# Micro2440.net
KiCad netlist of a schematic drawn in Altium Designer
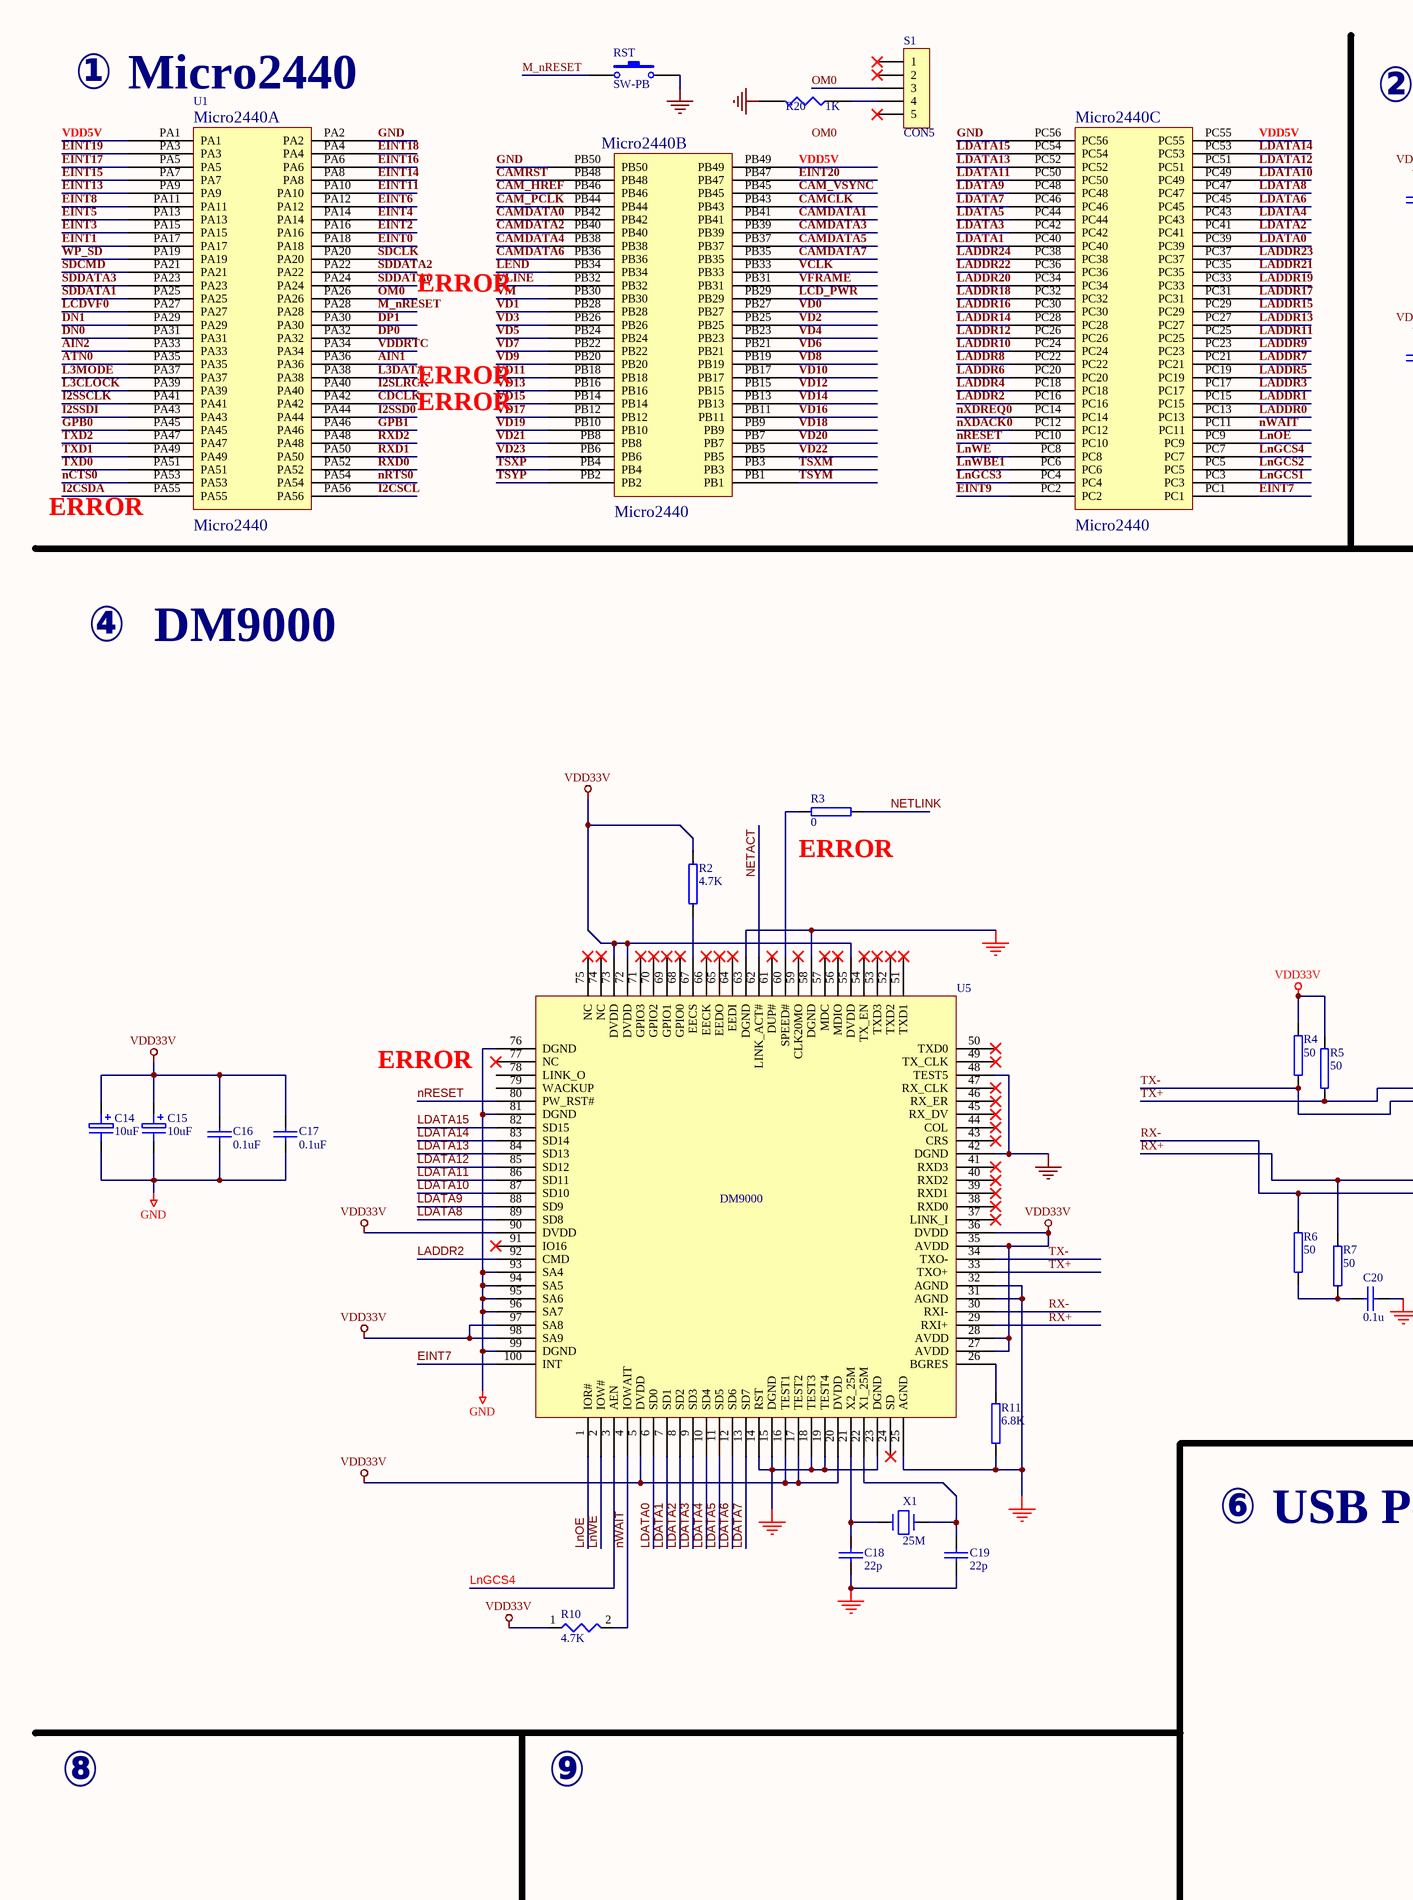
[diagram p0: Micro2440.SchDoc, left]
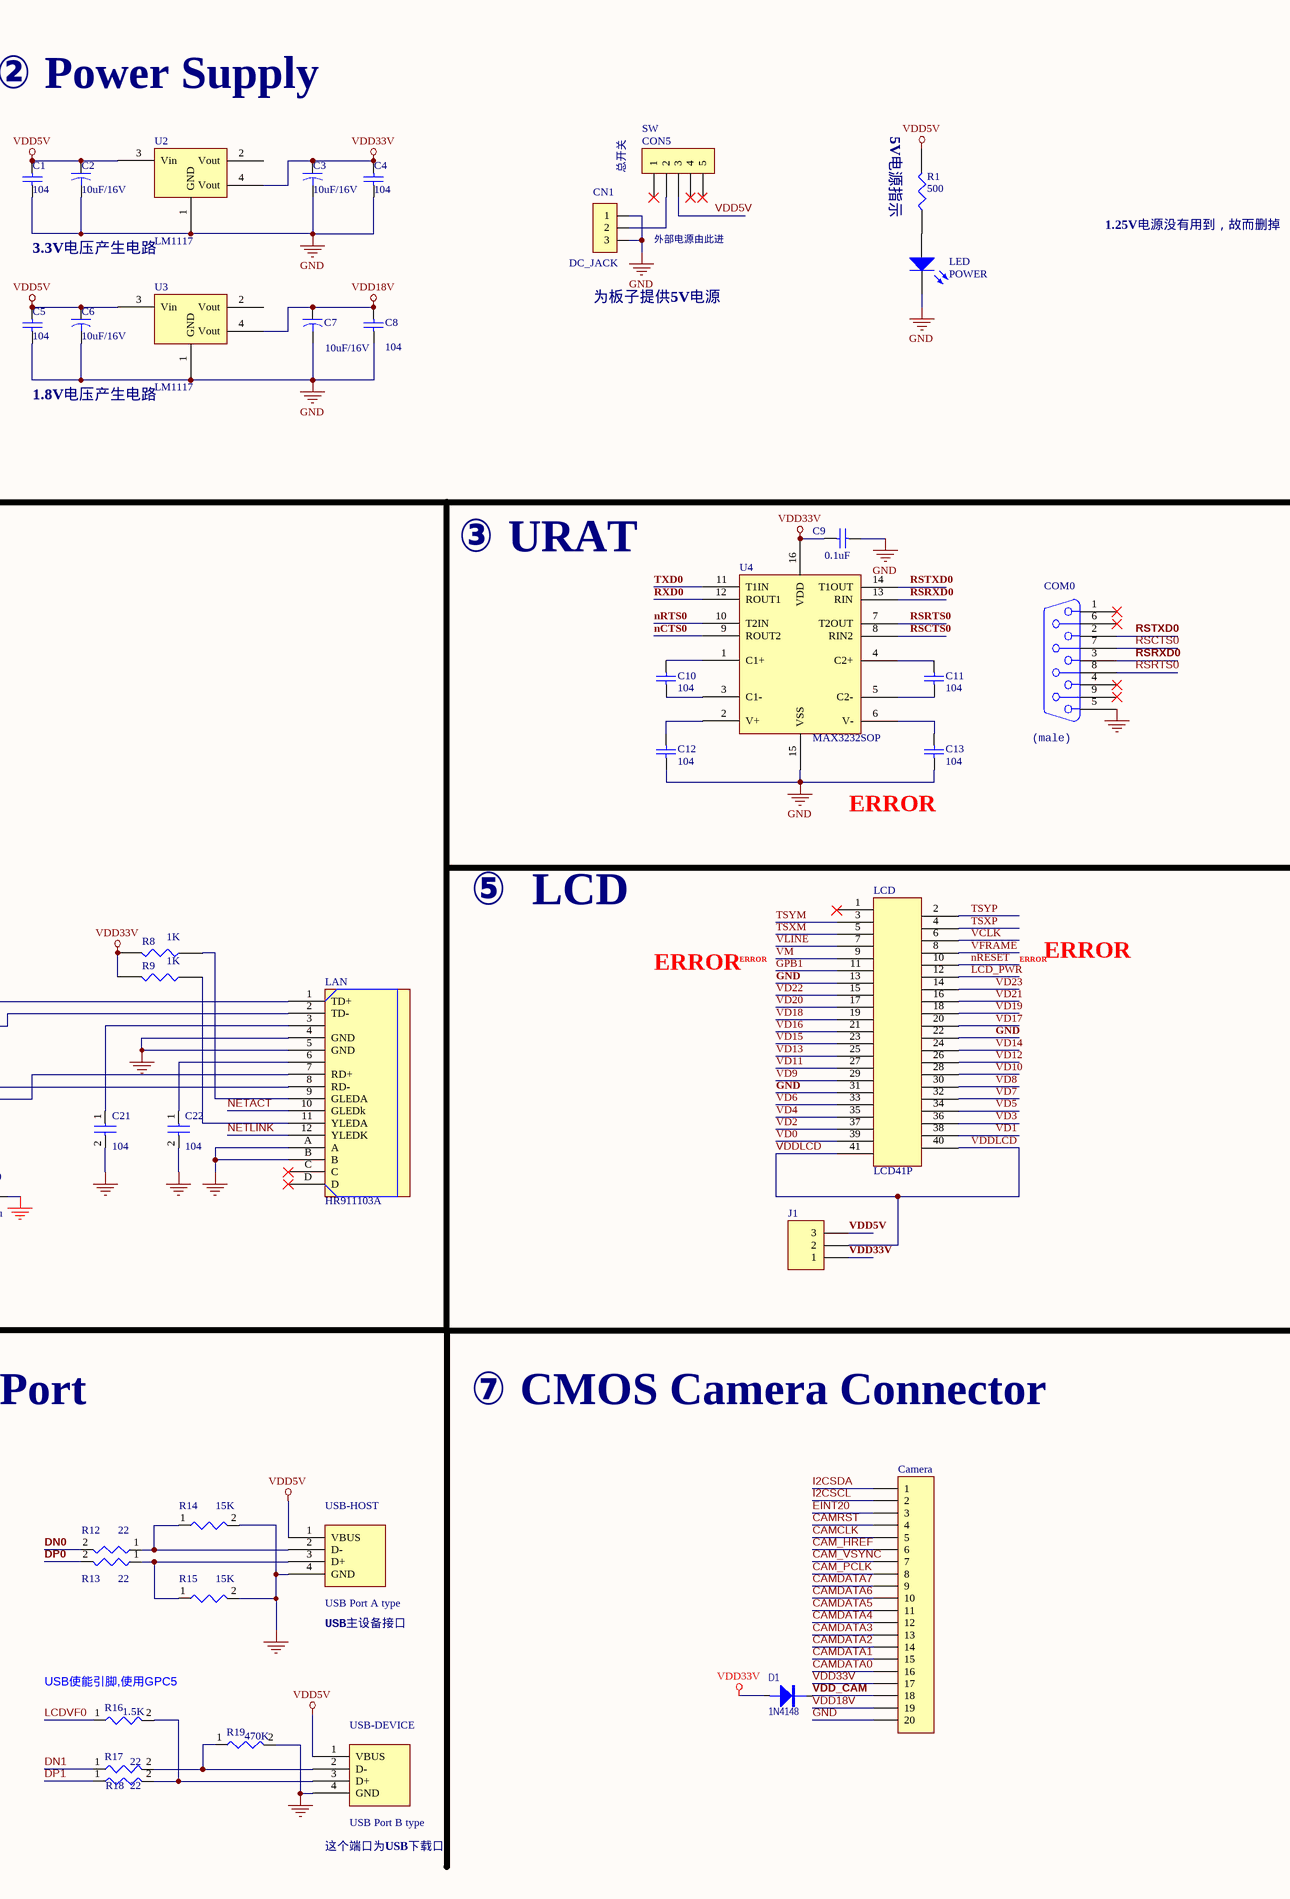
[diagram p1: Micro2440.SchDoc, right]

(export (version "E")
  (design (tool "Eeschema 10.0.6"))
  (components
    (comp (ref "C1")
      (value "104")
      (footprint "0603A")
      (description "Capacitor")
      (fields (field (name "Comment") "Cap") (field (name "PUBLISHER") "Altium Limited"))
      (libsource (lib "Miscellaneous Devices") (part "Cap"))
    )
    (comp (ref "C2")
      (value "10uF/16V")
      (footprint "C3216")
      (description "Capacitor")
      (fields (field (name "Comment") "Cap2") (field (name "PUBLISHER") "Altium Limited"))
      (libsource (lib "Miscellaneous Devices") (part "Cap2"))
    )
    (comp (ref "C3")
      (value "10uF/16V")
      (footprint "C3216")
      (description "Capacitor")
      (fields (field (name "Comment") "Cap2") (field (name "PUBLISHER") "Altium Limited"))
      (libsource (lib "Miscellaneous Devices") (part "Cap2"))
    )
    (comp (ref "C4")
      (value "104")
      (footprint "0603A")
      (description "Capacitor")
      (fields (field (name "Comment") "Cap") (field (name "PUBLISHER") "Altium Limited"))
      (libsource (lib "Miscellaneous Devices") (part "Cap"))
    )
    (comp (ref "C5")
      (value "104")
      (footprint "0603A")
      (description "Capacitor")
      (fields (field (name "Comment") "Cap") (field (name "PUBLISHER") "Altium Limited"))
      (libsource (lib "Miscellaneous Devices") (part "Cap"))
    )
    (comp (ref "C6")
      (value "10uF/16V")
      (footprint "C3216")
      (description "Capacitor")
      (fields (field (name "Comment") "Cap2") (field (name "PUBLISHER") "Altium Limited"))
      (libsource (lib "Miscellaneous Devices") (part "Cap2"))
    )
    (comp (ref "C7")
      (value "10uF/16V")
      (footprint "C3216")
      (description "Capacitor")
      (fields (field (name "Comment") "Cap2") (field (name "PUBLISHER") "Altium Limited"))
      (libsource (lib "Miscellaneous Devices") (part "Cap2"))
    )
    (comp (ref "C8")
      (value "104")
      (footprint "0603A")
      (description "Capacitor")
      (fields (field (name "Comment") "Cap") (field (name "PUBLISHER") "Altium Limited"))
      (libsource (lib "Miscellaneous Devices") (part "Cap"))
    )
    (comp (ref "C9")
      (value "0.1uF")
      (footprint "0603A")
      (description "Capacitor (Semiconductor SIM Model)")
      (fields (field (name "Comment") "Cap Semi") (field (name "PUBLISHER") "Altium Limited"))
      (libsource (lib "Miscellaneous Devices") (part "Cap Semi"))
    )
    (comp (ref "C10")
      (value "104")
      (footprint "0603A")
      (description "Capacitor (Semiconductor SIM Model)")
      (fields (field (name "Comment") "Cap Semi") (field (name "PUBLISHER") "Altium Limited"))
      (libsource (lib "Miscellaneous Devices") (part "Cap Semi"))
    )
    (comp (ref "C11")
      (value "104")
      (footprint "0603A")
      (description "Capacitor (Semiconductor SIM Model)")
      (fields (field (name "Comment") "Cap Semi") (field (name "PUBLISHER") "Altium Limited"))
      (libsource (lib "Miscellaneous Devices") (part "Cap Semi"))
    )
    (comp (ref "C12")
      (value "104")
      (footprint "0603A")
      (description "Capacitor (Semiconductor SIM Model)")
      (fields (field (name "Comment") "Cap Semi") (field (name "PUBLISHER") "Altium Limited"))
      (libsource (lib "Miscellaneous Devices") (part "Cap Semi"))
    )
    (comp (ref "C13")
      (value "104")
      (footprint "0603A")
      (description "Capacitor (Semiconductor SIM Model)")
      (fields (field (name "Comment") "Cap Semi") (field (name "PUBLISHER") "Altium Limited"))
      (libsource (lib "Miscellaneous Devices") (part "Cap Semi"))
    )
    (comp (ref "C14") (value "10uF") (footprint "C3216") (libsource (lib "*") (part "ELECTRO1")))
    (comp (ref "C15") (value "10uF") (footprint "C3216") (libsource (lib "*") (part "ELECTRO1")))
    (comp (ref "C16") (value "0.1uF") (footprint "0603A") (libsource (lib "*") (part "CAP")))
    (comp (ref "C17") (value "0.1uF") (footprint "0603A") (libsource (lib "*") (part "CAP")))
    (comp (ref "C18") (value "22p") (footprint "0603A") (libsource (lib "*") (part "CAP")))
    (comp (ref "C19") (value "22p") (footprint "0603A") (libsource (lib "*") (part "CAP")))
    (comp (ref "C20") (value "0.1u") (footprint "0603A") (libsource (lib "*") (part "CAP")))
    (comp (ref "C21") (value "104") (footprint "0603A") (libsource (lib "*") (part "CAP NP_0")))
    (comp (ref "C22") (value "104") (footprint "0603A") (libsource (lib "*") (part "CAP NP_0")))
    (comp (ref "Camera")
      (value "CON20")
      (footprint "IDC20SS")
      (description "Connector")
      (libsource (lib "*") (part "CON20"))
    )
    (comp (ref "CN1") (value "DC_JACK") (footprint "DC25") (libsource (lib "*") (part "CON3")))
    (comp (ref "COM0") (value "~") (footprint "DB9RA/M") (libsource (lib "*") (part "CONNECTOR DB9")))
    (comp (ref "D1") (value "1N4148") (footprint "D1206") (libsource (lib "*") (part "DIODE")))
    (comp (ref "J1")
      (value "~")
      (footprint "HDR1X3")
      (description "Header, 3-Pin")
      (fields (field (name "PUBLISHER") "Altium Limited"))
      (libsource (lib "Miscellaneous Connectors") (part "Header 3"))
    )
    (comp (ref "LAN") (value "HR911103A") (footprint "HR911103A") (libsource (lib "*") (part "HR911103A")))
    (comp (ref "LCD") (value "LCD41P") (footprint "DF9B-41P-1V2") (libsource (lib "*") (part "LCD41P")))
    (comp (ref "LED")
      (value "POWER")
      (footprint "LED")
      (description "Typical BLUE SiC LED")
      (fields (field (name "PUBLISHER") "Altium Limited"))
      (libsource (lib "Miscellaneous Devices") (part "LED3"))
    )
    (comp (ref "R1") (value "500") (footprint "0603R") (libsource (lib "*") (part "RES1")))
    (comp (ref "R2") (value "4.7K") (footprint "0603R") (libsource (lib "*") (part "RES2")))
    (comp (ref "R3") (value "0") (footprint "0603R") (libsource (lib "*") (part "RES2")))
    (comp (ref "R4") (value "50") (footprint "0603R") (libsource (lib "*") (part "RES2")))
    (comp (ref "R5") (value "50") (footprint "0603R") (libsource (lib "*") (part "RES2")))
    (comp (ref "R6") (value "50") (footprint "0603R") (libsource (lib "*") (part "RES2")))
    (comp (ref "R7") (value "50") (footprint "0603R") (libsource (lib "*") (part "RES2")))
    (comp (ref "R8") (value "1K") (footprint "0603R") (libsource (lib "*") (part "RES1")))
    (comp (ref "R9") (value "1K") (footprint "0603R") (libsource (lib "*") (part "RES1")))
    (comp (ref "R10") (value "4.7K") (footprint "0603R") (libsource (lib "*") (part "R_0")))
    (comp (ref "R11") (value "6.8K") (footprint "0603R") (libsource (lib "*") (part "RES2")))
    (comp (ref "R12") (value "22") (footprint "0603R") (libsource (lib "*") (part "RESISTOR_2")))
    (comp (ref "R13") (value "22") (footprint "0603R") (libsource (lib "*") (part "RESISTOR_2")))
    (comp (ref "R14") (value "15K") (footprint "0603R") (libsource (lib "*") (part "RESISTOR_2")))
    (comp (ref "R15") (value "15K") (footprint "0603R") (libsource (lib "*") (part "RESISTOR_2")))
    (comp (ref "R16") (value "1.5K") (footprint "0603R") (libsource (lib "*") (part "RESISTOR_2")))
    (comp (ref "R17") (value "22") (footprint "0603R") (libsource (lib "*") (part "RESISTOR_2")))
    (comp (ref "R18") (value "22") (footprint "0603R") (libsource (lib "*") (part "RESISTOR_2")))
    (comp (ref "R19") (value "470K") (footprint "0603R") (libsource (lib "*") (part "RESISTOR_2")))
    (comp (ref "R20") (value "1K") (footprint "0603R") (libsource (lib "*") (part "RES1")))
    (comp (ref "RST")
      (value "SW-PB")
      (footprint "RST")
      (description "Switch")
      (fields (field (name "PUBLISHER") "Altium Limited"))
      (libsource (lib "Miscellaneous Devices") (part "SW-PB"))
    )
    (comp (ref "S1")
      (value "CON5")
      (footprint "PCBComponent_1")
      (description "Connector")
      (libsource (lib "") (part "CON5_1"))
    )
    (comp (ref "SW")
      (value "CON5")
      (footprint "Micro2440_LIB:PCBComponent_1")
      (description "Connector")
      (libsource (lib "*") (part "CON5"))
    )
    (comp (ref "U1")
      (value "Micro2440")
      (footprint "Micro2440SDK:MICRO2440")
      (libsource (lib "MICRO2440_01") (part "Component_1"))
    )
    (comp (ref "U2") (value "LM1117") (footprint "SOT223S") (libsource (lib "MICRO2440_LIB") (part "LM1117")))
    (comp (ref "U3") (value "LM1117") (footprint "SOT223S") (libsource (lib "MICRO2440_LIB") (part "LM1117")))
    (comp (ref "U4")
      (value "MAX3232SOP")
      (footprint "SSOP16")
      (libsource (lib "MAX3232SOP") (part "Component_1"))
    )
    (comp (ref "U5") (value "DM9000") (footprint "QFP100") (libsource (lib "*") (part "DM9000")))
    (comp (ref "USB-DEVICE")
      (value "USB Port B type")
      (footprint "USB-B")
      (libsource (lib "*") (part "USBPORT"))
    )
    (comp (ref "USB-HOST")
      (value "USB Port A type")
      (footprint "USB-A")
      (libsource (lib "*") (part "USBPORT"))
    )
    (comp (ref "X1") (value "25M") (footprint "OSC2PR-1") (libsource (lib "*") (part "CRYSTAL")))
  )
  (nets
    (net (code "1") (name "/AIN1") (class "Default")
      (node (ref "U1") (pin "PA36") (pinfunction "PA36_PA36") (pintype "passive"))
    )
    (net (code "2") (name "/AIN2") (class "Default")
      (node (ref "U1") (pin "PA33") (pinfunction "PA33_PA33") (pintype "passive"))
    )
    (net (code "3") (name "/ATN0") (class "Default")
      (node (ref "U1") (pin "PA35") (pinfunction "PA35_PA35") (pintype "passive"))
    )
    (net (code "4") (name "/CAMCLK") (class "Default")
      (node (ref "Camera") (pin "5") (pinfunction "5_5") (pintype "passive"))
      (node (ref "U1") (pin "PB43") (pinfunction "PB43_PB43") (pintype "passive"))
    )
    (net (code "5") (name "/CAMDATA0") (class "Default")
      (node (ref "Camera") (pin "16") (pinfunction "16_16") (pintype "passive"))
      (node (ref "U1") (pin "PB42") (pinfunction "PB42_PB42") (pintype "passive"))
    )
    (net (code "6") (name "/CAMDATA1") (class "Default")
      (node (ref "Camera") (pin "15") (pinfunction "15_15") (pintype "passive"))
      (node (ref "U1") (pin "PB41") (pinfunction "PB41_PB41") (pintype "passive"))
    )
    (net (code "7") (name "/CAMDATA2") (class "Default")
      (node (ref "Camera") (pin "14") (pinfunction "14_14") (pintype "passive"))
      (node (ref "U1") (pin "PB40") (pinfunction "PB40_PB40") (pintype "passive"))
    )
    (net (code "8") (name "/CAMDATA3") (class "Default")
      (node (ref "Camera") (pin "13") (pinfunction "13_13") (pintype "passive"))
      (node (ref "U1") (pin "PB39") (pinfunction "PB39_PB39") (pintype "passive"))
    )
    (net (code "9") (name "/CAMDATA4") (class "Default")
      (node (ref "Camera") (pin "12") (pinfunction "12_12") (pintype "passive"))
      (node (ref "U1") (pin "PB38") (pinfunction "PB38_PB38") (pintype "passive"))
    )
    (net (code "10") (name "/CAMDATA5") (class "Default")
      (node (ref "Camera") (pin "11") (pinfunction "11_11") (pintype "passive"))
      (node (ref "U1") (pin "PB37") (pinfunction "PB37_PB37") (pintype "passive"))
    )
    (net (code "11") (name "/CAMDATA6") (class "Default")
      (node (ref "Camera") (pin "10") (pinfunction "10_10") (pintype "passive"))
      (node (ref "U1") (pin "PB36") (pinfunction "PB36_PB36") (pintype "passive"))
    )
    (net (code "12") (name "/CAMDATA7") (class "Default")
      (node (ref "Camera") (pin "9") (pinfunction "9_9") (pintype "passive"))
      (node (ref "U1") (pin "PB35") (pinfunction "PB35_PB35") (pintype "passive"))
    )
    (net (code "13") (name "/CAMRST") (class "Default")
      (node (ref "Camera") (pin "4") (pinfunction "4_4") (pintype "passive"))
      (node (ref "U1") (pin "PB48") (pinfunction "PB48_PB48") (pintype "passive"))
    )
    (net (code "14") (name "/CAM_HREF") (class "Default")
      (node (ref "Camera") (pin "6") (pinfunction "6_6") (pintype "passive"))
      (node (ref "U1") (pin "PB46") (pinfunction "PB46_PB46") (pintype "passive"))
    )
    (net (code "15") (name "/CAM_PCLK") (class "Default")
      (node (ref "Camera") (pin "8") (pinfunction "8_8") (pintype "passive"))
      (node (ref "U1") (pin "PB44") (pinfunction "PB44_PB44") (pintype "passive"))
    )
    (net (code "16") (name "/CAM_VSYNC") (class "Default")
      (node (ref "Camera") (pin "7") (pinfunction "7_7") (pintype "passive"))
      (node (ref "U1") (pin "PB45") (pinfunction "PB45_PB45") (pintype "passive"))
    )
    (net (code "17") (name "/CDCLK") (class "Default")
      (node (ref "U1") (pin "PA42") (pinfunction "PA42_PA42") (pintype "passive"))
    )
    (net (code "18") (name "/DN0") (class "Default")
      (node (ref "R12") (pin "2") (pinfunction "2_2") (pintype "passive"))
      (node (ref "U1") (pin "PA31") (pinfunction "PA31_PA31") (pintype "passive"))
    )
    (net (code "19") (name "/DN1") (class "Default")
      (node (ref "R17") (pin "1") (pinfunction "1_1") (pintype "passive"))
      (node (ref "U1") (pin "PA29") (pinfunction "PA29_PA29") (pintype "passive"))
    )
    (net (code "20") (name "/DP0") (class "Default")
      (node (ref "R13") (pin "2") (pinfunction "2_2") (pintype "passive"))
      (node (ref "U1") (pin "PA32") (pinfunction "PA32_PA32") (pintype "passive"))
    )
    (net (code "21") (name "/DP1") (class "Default")
      (node (ref "R18") (pin "1") (pinfunction "1_1") (pintype "passive"))
      (node (ref "U1") (pin "PA30") (pinfunction "PA30_PA30") (pintype "passive"))
    )
    (net (code "22") (name "/EINT0") (class "Default")
      (node (ref "U1") (pin "PA18") (pinfunction "PA18_PA18") (pintype "passive"))
    )
    (net (code "23") (name "/EINT1") (class "Default")
      (node (ref "U1") (pin "PA17") (pinfunction "PA17_PA17") (pintype "passive"))
    )
    (net (code "24") (name "/EINT2") (class "Default")
      (node (ref "U1") (pin "PA16") (pinfunction "PA16_PA16") (pintype "passive"))
    )
    (net (code "25") (name "/EINT3") (class "Default")
      (node (ref "U1") (pin "PA15") (pinfunction "PA15_PA15") (pintype "passive"))
    )
    (net (code "26") (name "/EINT4") (class "Default")
      (node (ref "U1") (pin "PA14") (pinfunction "PA14_PA14") (pintype "passive"))
    )
    (net (code "27") (name "/EINT5") (class "Default")
      (node (ref "U1") (pin "PA13") (pinfunction "PA13_PA13") (pintype "passive"))
    )
    (net (code "28") (name "/EINT6") (class "Default")
      (node (ref "U1") (pin "PA12") (pinfunction "PA12_PA12") (pintype "passive"))
    )
    (net (code "29") (name "/EINT7") (class "Default")
      (node (ref "U1") (pin "PC1") (pinfunction "PC1_PC1") (pintype "passive"))
      (node (ref "U5") (pin "100") (pinfunction "INT_100") (pintype "passive"))
    )
    (net (code "30") (name "/EINT8") (class "Default")
      (node (ref "U1") (pin "PA11") (pinfunction "PA11_PA11") (pintype "passive"))
    )
    (net (code "31") (name "/EINT9") (class "Default")
      (node (ref "U1") (pin "PC2") (pinfunction "PC2_PC2") (pintype "passive"))
    )
    (net (code "32") (name "/EINT11") (class "Default")
      (node (ref "U1") (pin "PA10") (pinfunction "PA10_PA10") (pintype "passive"))
    )
    (net (code "33") (name "/EINT13") (class "Default")
      (node (ref "U1") (pin "PA9") (pinfunction "PA9_PA9") (pintype "passive"))
    )
    (net (code "34") (name "/EINT14") (class "Default")
      (node (ref "U1") (pin "PA8") (pinfunction "PA8_PA8") (pintype "passive"))
    )
    (net (code "35") (name "/EINT15") (class "Default")
      (node (ref "U1") (pin "PA7") (pinfunction "PA7_PA7") (pintype "passive"))
    )
    (net (code "36") (name "/EINT16") (class "Default")
      (node (ref "U1") (pin "PA6") (pinfunction "PA6_PA6") (pintype "passive"))
    )
    (net (code "37") (name "/EINT17") (class "Default")
      (node (ref "U1") (pin "PA5") (pinfunction "PA5_PA5") (pintype "passive"))
    )
    (net (code "38") (name "/EINT18") (class "Default")
      (node (ref "U1") (pin "PA4") (pinfunction "PA4_PA4") (pintype "passive"))
    )
    (net (code "39") (name "/EINT19") (class "Default")
      (node (ref "U1") (pin "PA3") (pinfunction "PA3_PA3") (pintype "passive"))
    )
    (net (code "40") (name "/EINT20") (class "Default")
      (node (ref "Camera") (pin "3") (pinfunction "3_3") (pintype "passive"))
      (node (ref "U1") (pin "PB47") (pinfunction "PB47_PB47") (pintype "passive"))
    )
    (net (code "41") (name "/GPB0") (class "Default")
      (node (ref "U1") (pin "PA45") (pinfunction "PA45_PA45") (pintype "passive"))
    )
    (net (code "42") (name "/GPB1") (class "Default")
      (node (ref "LCD") (pin "11") (pintype "passive"))
      (node (ref "U1") (pin "PA46") (pinfunction "PA46_PA46") (pintype "passive"))
    )
    (net (code "43") (name "/I2CSCL") (class "Default")
      (node (ref "Camera") (pin "2") (pinfunction "2_2") (pintype "passive"))
      (node (ref "U1") (pin "PA56") (pinfunction "PA56_PA56") (pintype "passive"))
    )
    (net (code "44") (name "/I2CSDA") (class "Default")
      (node (ref "Camera") (pin "1") (pinfunction "1_1") (pintype "passive"))
      (node (ref "U1") (pin "PA55") (pinfunction "PA55_PA55") (pintype "passive"))
    )
    (net (code "45") (name "/I2SLRCK") (class "Default")
      (node (ref "U1") (pin "PA40") (pinfunction "PA40_PA40") (pintype "passive"))
    )
    (net (code "46") (name "/I2SSCLK") (class "Default")
      (node (ref "U1") (pin "PA41") (pinfunction "PA41_PA41") (pintype "passive"))
    )
    (net (code "47") (name "/I2SSD0") (class "Default")
      (node (ref "U1") (pin "PA44") (pinfunction "PA44_PA44") (pintype "passive"))
    )
    (net (code "48") (name "/I2SSDI") (class "Default")
      (node (ref "U1") (pin "PA43") (pinfunction "PA43_PA43") (pintype "passive"))
    )
    (net (code "49") (name "/L3CLOCK") (class "Default")
      (node (ref "U1") (pin "PA39") (pinfunction "PA39_PA39") (pintype "passive"))
    )
    (net (code "50") (name "/L3DATA") (class "Default")
      (node (ref "U1") (pin "PA38") (pinfunction "PA38_PA38") (pintype "passive"))
    )
    (net (code "51") (name "/L3MODE") (class "Default")
      (node (ref "U1") (pin "PA37") (pinfunction "PA37_PA37") (pintype "passive"))
    )
    (net (code "52") (name "/LADDR0") (class "Default")
      (node (ref "U1") (pin "PC13") (pinfunction "PC13_PC13") (pintype "passive"))
    )
    (net (code "53") (name "/LADDR1") (class "Default")
      (node (ref "U1") (pin "PC15") (pinfunction "PC15_PC15") (pintype "passive"))
    )
    (net (code "54") (name "/LADDR2") (class "Default")
      (node (ref "U1") (pin "PC16") (pinfunction "PC16_PC16") (pintype "passive"))
      (node (ref "U5") (pin "92") (pinfunction "CMD_92") (pintype "passive"))
    )
    (net (code "55") (name "/LADDR3") (class "Default")
      (node (ref "U1") (pin "PC17") (pinfunction "PC17_PC17") (pintype "passive"))
    )
    (net (code "56") (name "/LADDR4") (class "Default")
      (node (ref "U1") (pin "PC18") (pinfunction "PC18_PC18") (pintype "passive"))
    )
    (net (code "57") (name "/LADDR5") (class "Default")
      (node (ref "U1") (pin "PC19") (pinfunction "PC19_PC19") (pintype "passive"))
    )
    (net (code "58") (name "/LADDR6") (class "Default")
      (node (ref "U1") (pin "PC20") (pinfunction "PC20_PC20") (pintype "passive"))
    )
    (net (code "59") (name "/LADDR7") (class "Default")
      (node (ref "U1") (pin "PC21") (pinfunction "PC21_PC21") (pintype "passive"))
    )
    (net (code "60") (name "/LADDR8") (class "Default")
      (node (ref "U1") (pin "PC22") (pinfunction "PC22_PC22") (pintype "passive"))
    )
    (net (code "61") (name "/LADDR9") (class "Default")
      (node (ref "U1") (pin "PC23") (pinfunction "PC23_PC23") (pintype "passive"))
    )
    (net (code "62") (name "/LADDR10") (class "Default")
      (node (ref "U1") (pin "PC24") (pinfunction "PC24_PC24") (pintype "passive"))
    )
    (net (code "63") (name "/LADDR11") (class "Default")
      (node (ref "U1") (pin "PC25") (pinfunction "PC25_PC25") (pintype "passive"))
    )
    (net (code "64") (name "/LADDR12") (class "Default")
      (node (ref "U1") (pin "PC26") (pinfunction "PC26_PC26") (pintype "passive"))
    )
    (net (code "65") (name "/LADDR13") (class "Default")
      (node (ref "U1") (pin "PC27") (pinfunction "PC27_PC27") (pintype "passive"))
    )
    (net (code "66") (name "/LADDR14") (class "Default")
      (node (ref "U1") (pin "PC28") (pinfunction "PC28_PC28") (pintype "passive"))
    )
    (net (code "67") (name "/LADDR15") (class "Default")
      (node (ref "U1") (pin "PC29") (pinfunction "PC29_PC29") (pintype "passive"))
    )
    (net (code "68") (name "/LADDR16") (class "Default")
      (node (ref "U1") (pin "PC30") (pinfunction "PC30_PC30") (pintype "passive"))
    )
    (net (code "69") (name "/LADDR17") (class "Default")
      (node (ref "U1") (pin "PC31") (pinfunction "PC31_PC31") (pintype "passive"))
    )
    (net (code "70") (name "/LADDR18") (class "Default")
      (node (ref "U1") (pin "PC32") (pinfunction "PC32_PC32") (pintype "passive"))
    )
    (net (code "71") (name "/LADDR19") (class "Default")
      (node (ref "U1") (pin "PC33") (pinfunction "PC33_PC33") (pintype "passive"))
    )
    (net (code "72") (name "/LADDR20") (class "Default")
      (node (ref "U1") (pin "PC34") (pinfunction "PC34_PC34") (pintype "passive"))
    )
    (net (code "73") (name "/LADDR21") (class "Default")
      (node (ref "U1") (pin "PC35") (pinfunction "PC35_PC35") (pintype "passive"))
    )
    (net (code "74") (name "/LADDR22") (class "Default")
      (node (ref "U1") (pin "PC36") (pinfunction "PC36_PC36") (pintype "passive"))
    )
    (net (code "75") (name "/LADDR23") (class "Default")
      (node (ref "U1") (pin "PC37") (pinfunction "PC37_PC37") (pintype "passive"))
    )
    (net (code "76") (name "/LADDR24") (class "Default")
      (node (ref "U1") (pin "PC38") (pinfunction "PC38_PC38") (pintype "passive"))
    )
    (net (code "77") (name "/LCDVF0") (class "Default")
      (node (ref "R16") (pin "1") (pinfunction "1_1") (pintype "passive"))
      (node (ref "U1") (pin "PA27") (pinfunction "PA27_PA27") (pintype "passive"))
    )
    (net (code "78") (name "/LCD_PWR") (class "Default")
      (node (ref "LCD") (pin "12") (pintype "passive"))
      (node (ref "U1") (pin "PB29") (pinfunction "PB29_PB29") (pintype "passive"))
    )
    (net (code "79") (name "/LDATA0") (class "Default")
      (node (ref "U1") (pin "PC39") (pinfunction "PC39_PC39") (pintype "passive"))
      (node (ref "U5") (pin "6") (pinfunction "SD0_6") (pintype "passive"))
    )
    (net (code "80") (name "/LDATA1") (class "Default")
      (node (ref "U1") (pin "PC40") (pinfunction "PC40_PC40") (pintype "passive"))
      (node (ref "U5") (pin "7") (pinfunction "SD1_7") (pintype "passive"))
    )
    (net (code "81") (name "/LDATA2") (class "Default")
      (node (ref "U1") (pin "PC41") (pinfunction "PC41_PC41") (pintype "passive"))
      (node (ref "U5") (pin "8") (pinfunction "SD2_8") (pintype "passive"))
    )
    (net (code "82") (name "/LDATA3") (class "Default")
      (node (ref "U1") (pin "PC42") (pinfunction "PC42_PC42") (pintype "passive"))
      (node (ref "U5") (pin "9") (pinfunction "SD3_9") (pintype "passive"))
    )
    (net (code "83") (name "/LDATA4") (class "Default")
      (node (ref "U1") (pin "PC43") (pinfunction "PC43_PC43") (pintype "passive"))
      (node (ref "U5") (pin "10") (pinfunction "SD4_10") (pintype "passive"))
    )
    (net (code "84") (name "/LDATA5") (class "Default")
      (node (ref "U1") (pin "PC44") (pinfunction "PC44_PC44") (pintype "passive"))
      (node (ref "U5") (pin "11") (pinfunction "SD5_11") (pintype "passive"))
    )
    (net (code "85") (name "/LDATA6") (class "Default")
      (node (ref "U1") (pin "PC45") (pinfunction "PC45_PC45") (pintype "passive"))
      (node (ref "U5") (pin "12") (pinfunction "SD6_12") (pintype "passive"))
    )
    (net (code "86") (name "/LDATA7") (class "Default")
      (node (ref "U1") (pin "PC46") (pinfunction "PC46_PC46") (pintype "passive"))
      (node (ref "U5") (pin "13") (pinfunction "SD7_13") (pintype "passive"))
    )
    (net (code "87") (name "/LDATA8") (class "Default")
      (node (ref "U1") (pin "PC47") (pinfunction "PC47_PC47") (pintype "passive"))
      (node (ref "U5") (pin "89") (pinfunction "SD8_89") (pintype "passive"))
    )
    (net (code "88") (name "/LDATA9") (class "Default")
      (node (ref "U1") (pin "PC48") (pinfunction "PC48_PC48") (pintype "passive"))
      (node (ref "U5") (pin "88") (pinfunction "SD9_88") (pintype "passive"))
    )
    (net (code "89") (name "/LDATA10") (class "Default")
      (node (ref "U1") (pin "PC49") (pinfunction "PC49_PC49") (pintype "passive"))
      (node (ref "U5") (pin "87") (pinfunction "SD10_87") (pintype "passive"))
    )
    (net (code "90") (name "/LDATA11") (class "Default")
      (node (ref "U1") (pin "PC50") (pinfunction "PC50_PC50") (pintype "passive"))
      (node (ref "U5") (pin "86") (pinfunction "SD11_86") (pintype "passive"))
    )
    (net (code "91") (name "/LDATA12") (class "Default")
      (node (ref "U1") (pin "PC51") (pinfunction "PC51_PC51") (pintype "passive"))
      (node (ref "U5") (pin "85") (pinfunction "SD12_85") (pintype "passive"))
    )
    (net (code "92") (name "/LDATA13") (class "Default")
      (node (ref "U1") (pin "PC52") (pinfunction "PC52_PC52") (pintype "passive"))
      (node (ref "U5") (pin "84") (pinfunction "SD13_84") (pintype "passive"))
    )
    (net (code "93") (name "/LDATA14") (class "Default")
      (node (ref "U1") (pin "PC53") (pinfunction "PC53_PC53") (pintype "passive"))
      (node (ref "U5") (pin "83") (pinfunction "SD14_83") (pintype "passive"))
    )
    (net (code "94") (name "/LDATA15") (class "Default")
      (node (ref "U1") (pin "PC54") (pinfunction "PC54_PC54") (pintype "passive"))
      (node (ref "U5") (pin "82") (pinfunction "SD15_82") (pintype "passive"))
    )
    (net (code "95") (name "/LEND") (class "Default")
      (node (ref "U1") (pin "PB34") (pinfunction "PB34_PB34") (pintype "passive"))
    )
    (net (code "96") (name "/LnGCS1") (class "Default")
      (node (ref "U1") (pin "PC3") (pinfunction "PC3_PC3") (pintype "passive"))
    )
    (net (code "97") (name "/LnGCS2") (class "Default")
      (node (ref "U1") (pin "PC5") (pinfunction "PC5_PC5") (pintype "passive"))
    )
    (net (code "98") (name "/LnGCS3") (class "Default")
      (node (ref "U1") (pin "PC4") (pinfunction "PC4_PC4") (pintype "passive"))
    )
    (net (code "99") (name "/LnGCS4") (class "Default")
      (node (ref "U1") (pin "PC7") (pinfunction "PC7_PC7") (pintype "passive"))
      (node (ref "U5") (pin "3") (pinfunction "AEN_3") (pintype "passive"))
    )
    (net (code "100") (name "/LnOE") (class "Default")
      (node (ref "U1") (pin "PC9") (pinfunction "PC9_PC9") (pintype "passive"))
      (node (ref "U5") (pin "1") (pinfunction "IOR#_1") (pintype "passive"))
    )
    (net (code "101") (name "/LnWBE1") (class "Default")
      (node (ref "U1") (pin "PC6") (pinfunction "PC6_PC6") (pintype "passive"))
    )
    (net (code "102") (name "/LnWE") (class "Default")
      (node (ref "U1") (pin "PC8") (pinfunction "PC8_PC8") (pintype "passive"))
      (node (ref "U5") (pin "2") (pinfunction "IOW#_2") (pintype "passive"))
    )
    (net (code "103") (name "/M_nRESET") (class "Default")
      (node (ref "RST") (pin "1") (pinfunction "1_1") (pintype "passive"))
      (node (ref "U1") (pin "PA28") (pinfunction "PA28_PA28") (pintype "passive"))
    )
    (net (code "104") (name "/NETACT") (class "Default")
      (node (ref "LAN") (pin "10") (pinfunction "GLEDk_10") (pintype "passive"))
      (node (ref "U5") (pin "62") (pinfunction "LINK_ACT#_62") (pintype "passive"))
    )
    (net (code "105") (name "/NETLINK") (class "Default")
      (node (ref "LAN") (pin "12") (pinfunction "YLEDK_12") (pintype "passive"))
      (node (ref "R3") (pin "1") (pintype "passive"))
    )
    (net (code "106") (name "/OM0") (class "Default")
      (node (ref "S1") (pin "3") (pinfunction "3_3") (pintype "passive"))
      (node (ref "U1") (pin "PA26") (pinfunction "PA26_PA26") (pintype "passive"))
    )
    (net (code "107") (name "/RSCTS0") (class "Default")
      (node (ref "COM0") (pin "7") (pinfunction "7_7") (pintype "passive"))
      (node (ref "U4") (pin "8") (pinfunction "RIN2_8") (pintype "passive"))
    )
    (net (code "108") (name "/RSRTS0") (class "Default")
      (node (ref "COM0") (pin "8") (pinfunction "8_8") (pintype "passive"))
      (node (ref "U4") (pin "7") (pinfunction "T2OUT_7") (pintype "passive"))
    )
    (net (code "109") (name "/RSRXD0") (class "Default")
      (node (ref "COM0") (pin "3") (pinfunction "3_3") (pintype "passive"))
      (node (ref "U4") (pin "13") (pinfunction "RIN_13") (pintype "passive"))
    )
    (net (code "110") (name "/RSTXD0") (class "Default")
      (node (ref "COM0") (pin "2") (pinfunction "2_2") (pintype "passive"))
      (node (ref "U4") (pin "14") (pinfunction "T1OUT_14") (pintype "passive"))
    )
    (net (code "111") (name "/RX+") (class "Default")
      (node (ref "LAN") (pin "8") (pinfunction "RD-_8") (pintype "passive"))
      (node (ref "R7") (pin "2") (pintype "passive"))
      (node (ref "U5") (pin "29") (pinfunction "RXI+_29") (pintype "passive"))
    )
    (net (code "112") (name "/RX-") (class "Default")
      (node (ref "LAN") (pin "7") (pinfunction "RD+_7") (pintype "passive"))
      (node (ref "R6") (pin "2") (pintype "passive"))
      (node (ref "U5") (pin "30") (pinfunction "RXI-_30") (pintype "passive"))
    )
    (net (code "113") (name "/RXD0") (class "Default")
      (node (ref "U1") (pin "PA52") (pinfunction "PA52_PA52") (pintype "passive"))
      (node (ref "U4") (pin "12") (pinfunction "ROUT1_12") (pintype "passive"))
    )
    (net (code "114") (name "/RXD1") (class "Default")
      (node (ref "U1") (pin "PA50") (pinfunction "PA50_PA50") (pintype "passive"))
    )
    (net (code "115") (name "/RXD2") (class "Default")
      (node (ref "U1") (pin "PA48") (pinfunction "PA48_PA48") (pintype "passive"))
    )
    (net (code "116") (name "/SDCLK") (class "Default")
      (node (ref "U1") (pin "PA20") (pinfunction "PA20_PA20") (pintype "passive"))
    )
    (net (code "117") (name "/SDCMD") (class "Default")
      (node (ref "U1") (pin "PA21") (pinfunction "PA21_PA21") (pintype "passive"))
    )
    (net (code "118") (name "/SDDATA0") (class "Default")
      (node (ref "U1") (pin "PA24") (pinfunction "PA24_PA24") (pintype "passive"))
    )
    (net (code "119") (name "/SDDATA1") (class "Default")
      (node (ref "U1") (pin "PA25") (pinfunction "PA25_PA25") (pintype "passive"))
    )
    (net (code "120") (name "/SDDATA2") (class "Default")
      (node (ref "U1") (pin "PA22") (pinfunction "PA22_PA22") (pintype "passive"))
    )
    (net (code "121") (name "/SDDATA3") (class "Default")
      (node (ref "U1") (pin "PA23") (pinfunction "PA23_PA23") (pintype "passive"))
    )
    (net (code "122") (name "/TSXM") (class "Default")
      (node (ref "LCD") (pin "5") (pintype "passive"))
      (node (ref "U1") (pin "PB3") (pinfunction "PB3_PB3") (pintype "passive"))
    )
    (net (code "123") (name "/TSXP") (class "Default")
      (node (ref "LCD") (pin "4") (pintype "passive"))
      (node (ref "U1") (pin "PB4") (pinfunction "PB4_PB4") (pintype "passive"))
    )
    (net (code "124") (name "/TSYM") (class "Default")
      (node (ref "LCD") (pin "3") (pintype "passive"))
      (node (ref "U1") (pin "PB1") (pinfunction "PB1_PB1") (pintype "passive"))
    )
    (net (code "125") (name "/TSYP") (class "Default")
      (node (ref "LCD") (pin "2") (pintype "passive"))
      (node (ref "U1") (pin "PB2") (pinfunction "PB2_PB2") (pintype "passive"))
    )
    (net (code "126") (name "/TX+") (class "Default")
      (node (ref "LAN") (pin "1") (pinfunction "TD+_1") (pintype "passive"))
      (node (ref "R5") (pin "1") (pintype "passive"))
      (node (ref "U5") (pin "33") (pinfunction "TXO+_33") (pintype "passive"))
    )
    (net (code "127") (name "/TX-") (class "Default")
      (node (ref "LAN") (pin "2") (pinfunction "TD-_2") (pintype "passive"))
      (node (ref "R4") (pin "1") (pintype "passive"))
      (node (ref "U5") (pin "34") (pinfunction "TXO-_34") (pintype "passive"))
    )
    (net (code "128") (name "/TXD0") (class "Default")
      (node (ref "U1") (pin "PA51") (pinfunction "PA51_PA51") (pintype "passive"))
      (node (ref "U4") (pin "11") (pinfunction "T1IN_11") (pintype "passive"))
    )
    (net (code "129") (name "/TXD1") (class "Default")
      (node (ref "U1") (pin "PA49") (pinfunction "PA49_PA49") (pintype "passive"))
    )
    (net (code "130") (name "/TXD2") (class "Default")
      (node (ref "U1") (pin "PA47") (pinfunction "PA47_PA47") (pintype "passive"))
    )
    (net (code "131") (name "/VCLK") (class "Default")
      (node (ref "LCD") (pin "6") (pintype "passive"))
      (node (ref "U1") (pin "PB33") (pinfunction "PB33_PB33") (pintype "passive"))
    )
    (net (code "132") (name "/VD0") (class "Default")
      (node (ref "LCD") (pin "39") (pintype "passive"))
      (node (ref "U1") (pin "PB27") (pinfunction "PB27_PB27") (pintype "passive"))
    )
    (net (code "133") (name "/VD1") (class "Default")
      (node (ref "LCD") (pin "38") (pintype "passive"))
      (node (ref "U1") (pin "PB28") (pinfunction "PB28_PB28") (pintype "passive"))
    )
    (net (code "134") (name "/VD2") (class "Default")
      (node (ref "LCD") (pin "37") (pintype "passive"))
      (node (ref "U1") (pin "PB25") (pinfunction "PB25_PB25") (pintype "passive"))
    )
    (net (code "135") (name "/VD3") (class "Default")
      (node (ref "LCD") (pin "36") (pintype "passive"))
      (node (ref "U1") (pin "PB26") (pinfunction "PB26_PB26") (pintype "passive"))
    )
    (net (code "136") (name "/VD4") (class "Default")
      (node (ref "LCD") (pin "35") (pintype "passive"))
      (node (ref "U1") (pin "PB23") (pinfunction "PB23_PB23") (pintype "passive"))
    )
    (net (code "137") (name "/VD5") (class "Default")
      (node (ref "LCD") (pin "34") (pintype "passive"))
      (node (ref "U1") (pin "PB24") (pinfunction "PB24_PB24") (pintype "passive"))
    )
    (net (code "138") (name "/VD6") (class "Default")
      (node (ref "LCD") (pin "33") (pintype "passive"))
      (node (ref "U1") (pin "PB21") (pinfunction "PB21_PB21") (pintype "passive"))
    )
    (net (code "139") (name "/VD7") (class "Default")
      (node (ref "LCD") (pin "32") (pintype "passive"))
      (node (ref "U1") (pin "PB22") (pinfunction "PB22_PB22") (pintype "passive"))
    )
    (net (code "140") (name "/VD8") (class "Default")
      (node (ref "LCD") (pin "30") (pintype "passive"))
      (node (ref "U1") (pin "PB19") (pinfunction "PB19_PB19") (pintype "passive"))
    )
    (net (code "141") (name "/VD9") (class "Default")
      (node (ref "LCD") (pin "29") (pintype "passive"))
      (node (ref "U1") (pin "PB20") (pinfunction "PB20_PB20") (pintype "passive"))
    )
    (net (code "142") (name "/VD10") (class "Default")
      (node (ref "LCD") (pin "28") (pintype "passive"))
      (node (ref "U1") (pin "PB17") (pinfunction "PB17_PB17") (pintype "passive"))
    )
    (net (code "143") (name "/VD11") (class "Default")
      (node (ref "LCD") (pin "27") (pintype "passive"))
      (node (ref "U1") (pin "PB18") (pinfunction "PB18_PB18") (pintype "passive"))
    )
    (net (code "144") (name "/VD12") (class "Default")
      (node (ref "LCD") (pin "26") (pintype "passive"))
      (node (ref "U1") (pin "PB15") (pinfunction "PB15_PB15") (pintype "passive"))
    )
    (net (code "145") (name "/VD13") (class "Default")
      (node (ref "LCD") (pin "25") (pintype "passive"))
      (node (ref "U1") (pin "PB16") (pinfunction "PB16_PB16") (pintype "passive"))
    )
    (net (code "146") (name "/VD14") (class "Default")
      (node (ref "LCD") (pin "24") (pintype "passive"))
      (node (ref "U1") (pin "PB13") (pinfunction "PB13_PB13") (pintype "passive"))
    )
    (net (code "147") (name "/VD15") (class "Default")
      (node (ref "LCD") (pin "23") (pintype "passive"))
      (node (ref "U1") (pin "PB14") (pinfunction "PB14_PB14") (pintype "passive"))
    )
    (net (code "148") (name "/VD16") (class "Default")
      (node (ref "LCD") (pin "21") (pintype "passive"))
      (node (ref "U1") (pin "PB11") (pinfunction "PB11_PB11") (pintype "passive"))
    )
    (net (code "149") (name "/VD17") (class "Default")
      (node (ref "LCD") (pin "20") (pintype "passive"))
      (node (ref "U1") (pin "PB12") (pinfunction "PB12_PB12") (pintype "passive"))
    )
    (net (code "150") (name "/VD18") (class "Default")
      (node (ref "LCD") (pin "19") (pintype "passive"))
      (node (ref "U1") (pin "PB9") (pinfunction "PB9_PB9") (pintype "passive"))
    )
    (net (code "151") (name "/VD19") (class "Default")
      (node (ref "LCD") (pin "18") (pintype "passive"))
      (node (ref "U1") (pin "PB10") (pinfunction "PB10_PB10") (pintype "passive"))
    )
    (net (code "152") (name "/VD20") (class "Default")
      (node (ref "LCD") (pin "17") (pintype "passive"))
      (node (ref "U1") (pin "PB7") (pinfunction "PB7_PB7") (pintype "passive"))
    )
    (net (code "153") (name "/VD21") (class "Default")
      (node (ref "LCD") (pin "16") (pintype "passive"))
      (node (ref "U1") (pin "PB8") (pinfunction "PB8_PB8") (pintype "passive"))
    )
    (net (code "154") (name "/VD22") (class "Default")
      (node (ref "LCD") (pin "15") (pintype "passive"))
      (node (ref "U1") (pin "PB5") (pinfunction "PB5_PB5") (pintype "passive"))
    )
    (net (code "155") (name "/VD23") (class "Default")
      (node (ref "LCD") (pin "14") (pintype "passive"))
      (node (ref "U1") (pin "PB6") (pinfunction "PB6_PB6") (pintype "passive"))
    )
    (net (code "156") (name "/VDDLCD") (class "Default")
      (node (ref "J1") (pin "2") (pinfunction "2_2") (pintype "passive"))
      (node (ref "LCD") (pin "40") (pintype "passive"))
      (node (ref "LCD") (pin "41") (pintype "passive"))
    )
    (net (code "157") (name "/VDDRTC") (class "Default")
      (node (ref "U1") (pin "PA34") (pinfunction "PA34_PA34") (pintype "passive"))
    )
    (net (code "158") (name "/VDD_CAM") (class "Default")
      (node (ref "Camera") (pin "18") (pinfunction "18_18") (pintype "passive"))
      (node (ref "D1") (pin "2") (pinfunction "2_2") (pintype "passive"))
    )
    (net (code "159") (name "/VFRAME") (class "Default")
      (node (ref "LCD") (pin "8") (pintype "passive"))
      (node (ref "U1") (pin "PB31") (pinfunction "PB31_PB31") (pintype "passive"))
    )
    (net (code "160") (name "/VLINE") (class "Default")
      (node (ref "LCD") (pin "7") (pintype "passive"))
      (node (ref "U1") (pin "PB32") (pinfunction "PB32_PB32") (pintype "passive"))
    )
    (net (code "161") (name "/VM") (class "Default")
      (node (ref "LCD") (pin "9") (pintype "passive"))
      (node (ref "U1") (pin "PB30") (pinfunction "PB30_PB30") (pintype "passive"))
    )
    (net (code "162") (name "/WP_SD") (class "Default")
      (node (ref "U1") (pin "PA19") (pinfunction "PA19_PA19") (pintype "passive"))
    )
    (net (code "163") (name "/nCTS0") (class "Default")
      (node (ref "U1") (pin "PA53") (pinfunction "PA53_PA53") (pintype "passive"))
      (node (ref "U4") (pin "9") (pinfunction "ROUT2_9") (pintype "passive"))
    )
    (net (code "164") (name "/nRESET") (class "Default")
      (node (ref "LCD") (pin "10") (pintype "passive"))
      (node (ref "U1") (pin "PC10") (pinfunction "PC10_PC10") (pintype "passive"))
      (node (ref "U5") (pin "80") (pinfunction "PW_RST#_80") (pintype "passive"))
    )
    (net (code "165") (name "/nRTS0") (class "Default")
      (node (ref "U1") (pin "PA54") (pinfunction "PA54_PA54") (pintype "passive"))
      (node (ref "U4") (pin "10") (pinfunction "T2IN_10") (pintype "passive"))
    )
    (net (code "166") (name "/nWAIT") (class "Default")
      (node (ref "R10") (pin "2") (pinfunction "2_2") (pintype "passive"))
      (node (ref "U1") (pin "PC11") (pinfunction "PC11_PC11") (pintype "passive"))
      (node (ref "U5") (pin "4") (pinfunction "IOWAIT_4") (pintype "passive"))
    )
    (net (code "167") (name "/nXDACK0") (class "Default")
      (node (ref "U1") (pin "PC12") (pinfunction "PC12_PC12") (pintype "passive"))
    )
    (net (code "168") (name "/nXDREQ0") (class "Default")
      (node (ref "U1") (pin "PC14") (pinfunction "PC14_PC14") (pintype "passive"))
    )
    (net (code "169") (name "GND") (class "Default")
      (node (ref "C1") (pin "2") (pinfunction "2_2") (pintype "passive"))
      (node (ref "C12") (pin "1") (pinfunction "1_1") (pintype "passive"))
      (node (ref "C13") (pin "1") (pinfunction "1_1") (pintype "passive"))
      (node (ref "C14") (pin "2") (pintype "passive"))
      (node (ref "C15") (pin "2") (pintype "passive"))
      (node (ref "C16") (pin "2") (pintype "passive"))
      (node (ref "C17") (pin "2") (pintype "passive"))
      (node (ref "C18") (pin "2") (pintype "passive"))
      (node (ref "C19") (pin "2") (pintype "passive"))
      (node (ref "C2") (pin "2") (pinfunction "2_2") (pintype "passive"))
      (node (ref "C20") (pin "2") (pintype "passive"))
      (node (ref "C21") (pin "2") (pinfunction "2_2") (pintype "passive"))
      (node (ref "C22") (pin "2") (pinfunction "2_2") (pintype "passive"))
      (node (ref "C3") (pin "2") (pinfunction "2_2") (pintype "passive"))
      (node (ref "C4") (pin "2") (pinfunction "2_2") (pintype "passive"))
      (node (ref "C5") (pin "2") (pinfunction "2_2") (pintype "passive"))
      (node (ref "C6") (pin "2") (pinfunction "2_2") (pintype "passive"))
      (node (ref "C7") (pin "2") (pinfunction "2_2") (pintype "passive"))
      (node (ref "C8") (pin "2") (pinfunction "2_2") (pintype "passive"))
      (node (ref "C9") (pin "2") (pinfunction "2_2") (pintype "passive"))
      (node (ref "CN1") (pin "1") (pinfunction "1_1") (pintype "passive"))
      (node (ref "CN1") (pin "3") (pinfunction "3_3") (pintype "passive"))
      (node (ref "COM0") (pin "5") (pinfunction "5_5") (pintype "passive"))
      (node (ref "Camera") (pin "20") (pinfunction "20_20") (pintype "passive"))
      (node (ref "LAN") (pin "4") (pinfunction "GND_4") (pintype "passive"))
      (node (ref "LAN") (pin "5") (pinfunction "GND_5") (pintype "passive"))
      (node (ref "LAN") (pin "A") (pinfunction "A_A") (pintype "passive"))
      (node (ref "LAN") (pin "B") (pinfunction "B_B") (pintype "passive"))
      (node (ref "LCD") (pin "13") (pintype "passive"))
      (node (ref "LCD") (pin "22") (pintype "passive"))
      (node (ref "LCD") (pin "31") (pintype "passive"))
      (node (ref "LED") (pin "2") (pinfunction "K_2") (pintype "passive"))
      (node (ref "R11") (pin "1") (pintype "passive"))
      (node (ref "R14") (pin "2") (pinfunction "2_2") (pintype "passive"))
      (node (ref "R15") (pin "2") (pinfunction "2_2") (pintype "passive"))
      (node (ref "R19") (pin "2") (pinfunction "2_2") (pintype "passive"))
      (node (ref "R20") (pin "2") (pinfunction "2_2") (pintype "passive"))
      (node (ref "RST") (pin "2") (pinfunction "2_2") (pintype "passive"))
      (node (ref "U1") (pin "PA2") (pinfunction "PA2_PA2") (pintype "passive"))
      (node (ref "U1") (pin "PB50") (pinfunction "PB50_PB50") (pintype "passive"))
      (node (ref "U1") (pin "PC56") (pinfunction "PC56_PC56") (pintype "passive"))
      (node (ref "U2") (pin "1") (pinfunction "GND_1") (pintype "passive"))
      (node (ref "U3") (pin "1") (pinfunction "GND_1") (pintype "passive"))
      (node (ref "U4") (pin "15") (pinfunction "VSS_15") (pintype "passive"))
      (node (ref "U5") (pin "14") (pinfunction "RST_14") (pintype "passive"))
      (node (ref "U5") (pin "15") (pinfunction "DGND_15") (pintype "passive"))
      (node (ref "U5") (pin "18") (pinfunction "TEST3_18") (pintype "passive"))
      (node (ref "U5") (pin "19") (pinfunction "TEST4_19") (pintype "passive"))
      (node (ref "U5") (pin "23") (pinfunction "DGND_23") (pintype "passive"))
      (node (ref "U5") (pin "25") (pinfunction "AGND_25") (pintype "passive"))
      (node (ref "U5") (pin "31") (pinfunction "AGND_31") (pintype "passive"))
      (node (ref "U5") (pin "32") (pinfunction "AGND_32") (pintype "passive"))
      (node (ref "U5") (pin "42") (pinfunction "DGND_42") (pintype "passive"))
      (node (ref "U5") (pin "48") (pinfunction "TEST5_48") (pintype "passive"))
      (node (ref "U5") (pin "58") (pinfunction "DGND_58") (pintype "passive"))
      (node (ref "U5") (pin "63") (pinfunction "DGND_63") (pintype "passive"))
      (node (ref "U5") (pin "76") (pinfunction "DGND_76") (pintype "passive"))
      (node (ref "U5") (pin "81") (pinfunction "DGND_81") (pintype "passive"))
      (node (ref "U5") (pin "93") (pinfunction "SA4_93") (pintype "passive"))
      (node (ref "U5") (pin "94") (pinfunction "SA5_94") (pintype "passive"))
      (node (ref "U5") (pin "95") (pinfunction "SA6_95") (pintype "passive"))
      (node (ref "U5") (pin "96") (pinfunction "SA7_96") (pintype "passive"))
      (node (ref "U5") (pin "99") (pinfunction "DGND_99") (pintype "passive"))
      (node (ref "USB-DEVICE") (pin "4") (pinfunction "GND_4") (pintype "passive"))
      (node (ref "USB-HOST") (pin "4") (pinfunction "GND_4") (pintype "passive"))
    )
    (net (code "170") (name "Net-(C20-Pad1)") (class "Default")
      (node (ref "C20") (pin "1") (pintype "passive"))
      (node (ref "R6") (pin "1") (pintype "passive"))
      (node (ref "R7") (pin "1") (pintype "passive"))
    )
    (net (code "171") (name "Net-(C21-Pad1)") (class "Default")
      (node (ref "C21") (pin "1") (pinfunction "1_1") (pintype "passive"))
      (node (ref "LAN") (pin "3") (pintype "passive"))
    )
    (net (code "172") (name "Net-(C22-Pad1)") (class "Default")
      (node (ref "C22") (pin "1") (pinfunction "1_1") (pintype "passive"))
      (node (ref "LAN") (pin "6") (pintype "passive"))
    )
    (net (code "173") (name "Net-(CN1-Pad2)") (class "Default")
      (node (ref "CN1") (pin "2") (pinfunction "2_2") (pintype "passive"))
      (node (ref "SW") (pin "2") (pinfunction "2_2") (pintype "passive"))
    )
    (net (code "174") (name "Net-(LAN-GLEDA)") (class "Default")
      (node (ref "LAN") (pin "9") (pinfunction "GLEDA_9") (pintype "passive"))
      (node (ref "R8") (pin "1") (pinfunction "1_1") (pintype "passive"))
    )
    (net (code "175") (name "Net-(LAN-YLEDA)") (class "Default")
      (node (ref "LAN") (pin "11") (pinfunction "YLEDA_11") (pintype "passive"))
      (node (ref "R9") (pin "1") (pinfunction "1_1") (pintype "passive"))
    )
    (net (code "176") (name "Net-(LED-A)") (class "Default")
      (node (ref "LED") (pin "1") (pinfunction "A_1") (pintype "passive"))
      (node (ref "R1") (pin "1") (pinfunction "1_1") (pintype "passive"))
    )
    (net (code "177") (name "Net-(R20-Pad1)") (class "Default")
      (node (ref "R20") (pin "1") (pinfunction "1_1") (pintype "passive"))
      (node (ref "S1") (pin "4") (pinfunction "4_4") (pintype "passive"))
    )
    (net (code "178") (name "Net-(U4-C1+)") (class "Default")
      (node (ref "C10") (pin "2") (pinfunction "2_2") (pintype "passive"))
      (node (ref "U4") (pin "1") (pinfunction "C1+_1") (pintype "passive"))
    )
    (net (code "179") (name "Net-(U4-C1-)") (class "Default")
      (node (ref "C10") (pin "1") (pinfunction "1_1") (pintype "passive"))
      (node (ref "U4") (pin "3") (pinfunction "C1-_3") (pintype "passive"))
    )
    (net (code "180") (name "Net-(U4-C2+)") (class "Default")
      (node (ref "C11") (pin "2") (pinfunction "2_2") (pintype "passive"))
      (node (ref "U4") (pin "4") (pinfunction "C2+_4") (pintype "passive"))
    )
    (net (code "181") (name "Net-(U4-C2-)") (class "Default")
      (node (ref "C11") (pin "1") (pinfunction "1_1") (pintype "passive"))
      (node (ref "U4") (pin "5") (pinfunction "C2-_5") (pintype "passive"))
    )
    (net (code "182") (name "Net-(U4-V+)") (class "Default")
      (node (ref "C12") (pin "2") (pinfunction "2_2") (pintype "passive"))
      (node (ref "U4") (pin "2") (pinfunction "V+_2") (pintype "passive"))
    )
    (net (code "183") (name "Net-(U4-V-)") (class "Default")
      (node (ref "C13") (pin "2") (pinfunction "2_2") (pintype "passive"))
      (node (ref "U4") (pin "6") (pinfunction "V-_6") (pintype "passive"))
    )
    (net (code "184") (name "Net-(U5-BGRES)") (class "Default")
      (node (ref "R11") (pin "2") (pintype "passive"))
      (node (ref "U5") (pin "26") (pinfunction "BGRES_26") (pintype "passive"))
    )
    (net (code "185") (name "Net-(U5-EECS)") (class "Default")
      (node (ref "R2") (pin "1") (pintype "passive"))
      (node (ref "U5") (pin "67") (pinfunction "EECS_67") (pintype "passive"))
    )
    (net (code "186") (name "Net-(U5-SPEED#)") (class "Default")
      (node (ref "R3") (pin "2") (pintype "passive"))
      (node (ref "U5") (pin "60") (pinfunction "SPEED#_60") (pintype "passive"))
    )
    (net (code "187") (name "Net-(U5-X1_25M)") (class "Default")
      (node (ref "C19") (pin "1") (pintype "passive"))
      (node (ref "U5") (pin "22") (pinfunction "X1_25M_22") (pintype "passive"))
      (node (ref "X1") (pin "2") (pintype "passive"))
    )
    (net (code "188") (name "Net-(U5-X2_25M)") (class "Default")
      (node (ref "C18") (pin "1") (pintype "passive"))
      (node (ref "U5") (pin "21") (pinfunction "X2_25M_21") (pintype "passive"))
      (node (ref "X1") (pin "1") (pintype "passive"))
    )
    (net (code "189") (name "Net-(USB-DEVICE-D+)") (class "Default")
      (node (ref "R16") (pin "2") (pinfunction "2_2") (pintype "passive"))
      (node (ref "R18") (pin "2") (pinfunction "2_2") (pintype "passive"))
      (node (ref "USB-DEVICE") (pin "3") (pinfunction "D+_3") (pintype "passive"))
    )
    (net (code "190") (name "Net-(USB-DEVICE-D-)") (class "Default")
      (node (ref "R17") (pin "2") (pinfunction "2_2") (pintype "passive"))
      (node (ref "R19") (pin "1") (pinfunction "1_1") (pintype "passive"))
      (node (ref "USB-DEVICE") (pin "2") (pinfunction "D-_2") (pintype "passive"))
    )
    (net (code "191") (name "Net-(USB-HOST-D+)") (class "Default")
      (node (ref "R13") (pin "1") (pinfunction "1_1") (pintype "passive"))
      (node (ref "R15") (pin "1") (pinfunction "1_1") (pintype "passive"))
      (node (ref "USB-HOST") (pin "3") (pinfunction "D+_3") (pintype "passive"))
    )
    (net (code "192") (name "Net-(USB-HOST-D-)") (class "Default")
      (node (ref "R12") (pin "1") (pinfunction "1_1") (pintype "passive"))
      (node (ref "R14") (pin "1") (pinfunction "1_1") (pintype "passive"))
      (node (ref "USB-HOST") (pin "2") (pinfunction "D-_2") (pintype "passive"))
    )
    (net (code "193") (name "VDD5V") (class "Default")
      (node (ref "C1") (pin "1") (pinfunction "1_1") (pintype "passive"))
      (node (ref "C2") (pin "1") (pinfunction "1_1") (pintype "passive"))
      (node (ref "C5") (pin "1") (pinfunction "1_1") (pintype "passive"))
      (node (ref "C6") (pin "1") (pinfunction "1_1") (pintype "passive"))
      (node (ref "J1") (pin "3") (pinfunction "3_3") (pintype "passive"))
      (node (ref "R1") (pin "2") (pinfunction "2_2") (pintype "passive"))
      (node (ref "SW") (pin "3") (pinfunction "3_3") (pintype "passive"))
      (node (ref "U1") (pin "PA1") (pinfunction "PA1_PA1") (pintype "passive"))
      (node (ref "U1") (pin "PB49") (pinfunction "PB49_PB49") (pintype "passive"))
      (node (ref "U1") (pin "PC55") (pinfunction "PC55_PC55") (pintype "passive"))
      (node (ref "U2") (pin "3") (pinfunction "Vin_3") (pintype "passive"))
      (node (ref "U3") (pin "3") (pinfunction "Vin_3") (pintype "passive"))
      (node (ref "USB-DEVICE") (pin "1") (pinfunction "VBUS_1") (pintype "passive"))
      (node (ref "USB-HOST") (pin "1") (pinfunction "VBUS_1") (pintype "passive"))
    )
    (net (code "194") (name "VDD18V") (class "Default")
      (node (ref "C7") (pin "1") (pinfunction "1_1") (pintype "passive"))
      (node (ref "C8") (pin "1") (pinfunction "1_1") (pintype "passive"))
      (node (ref "Camera") (pin "19") (pinfunction "19_19") (pintype "passive"))
      (node (ref "U3") (pin "4") (pinfunction "Vout_4") (pintype "passive"))
    )
    (net (code "195") (name "VDD33V") (class "Default")
      (node (ref "C14") (pin "1") (pintype "passive"))
      (node (ref "C15") (pin "1") (pintype "passive"))
      (node (ref "C16") (pin "1") (pintype "passive"))
      (node (ref "C17") (pin "1") (pintype "passive"))
      (node (ref "C3") (pin "1") (pinfunction "1_1") (pintype "passive"))
      (node (ref "C4") (pin "1") (pinfunction "1_1") (pintype "passive"))
      (node (ref "C9") (pin "1") (pinfunction "1_1") (pintype "passive"))
      (node (ref "Camera") (pin "17") (pinfunction "17_17") (pintype "passive"))
      (node (ref "D1") (pin "1") (pinfunction "1_1") (pintype "passive"))
      (node (ref "J1") (pin "1") (pinfunction "1_1") (pintype "passive"))
      (node (ref "R10") (pin "1") (pinfunction "1_1") (pintype "passive"))
      (node (ref "R2") (pin "2") (pintype "passive"))
      (node (ref "R4") (pin "2") (pintype "passive"))
      (node (ref "R5") (pin "2") (pintype "passive"))
      (node (ref "R8") (pin "2") (pinfunction "2_2") (pintype "passive"))
      (node (ref "R9") (pin "2") (pinfunction "2_2") (pintype "passive"))
      (node (ref "U2") (pin "4") (pinfunction "Vout_4") (pintype "passive"))
      (node (ref "U4") (pin "16") (pinfunction "VDD_16") (pintype "passive"))
      (node (ref "U5") (pin "16") (pinfunction "TEST1_16") (pintype "passive"))
      (node (ref "U5") (pin "17") (pinfunction "TEST2_17") (pintype "passive"))
      (node (ref "U5") (pin "20") (pinfunction "DVDD_20") (pintype "passive"))
      (node (ref "U5") (pin "27") (pinfunction "AVDD_27") (pintype "passive"))
      (node (ref "U5") (pin "28") (pinfunction "AVDD_28") (pintype "passive"))
      (node (ref "U5") (pin "35") (pinfunction "AVDD_35") (pintype "passive"))
      (node (ref "U5") (pin "36") (pinfunction "DVDD_36") (pintype "passive"))
      (node (ref "U5") (pin "5") (pinfunction "DVDD_5") (pintype "passive"))
      (node (ref "U5") (pin "55") (pinfunction "DVDD_55") (pintype "passive"))
      (node (ref "U5") (pin "72") (pinfunction "DVDD_72") (pintype "passive"))
      (node (ref "U5") (pin "73") (pinfunction "DVDD_73") (pintype "passive"))
      (node (ref "U5") (pin "90") (pinfunction "DVDD_90") (pintype "passive"))
      (node (ref "U5") (pin "97") (pinfunction "SA8_97") (pintype "passive"))
      (node (ref "U5") (pin "98") (pinfunction "SA9_98") (pintype "passive"))
    )
    (net (code "196") (name "unconnected-(COM0-Pad1)") (class "Default")
      (node (ref "COM0") (pin "1") (pinfunction "1_1") (pintype "passive+no_connect"))
    )
    (net (code "197") (name "unconnected-(COM0-Pad4)") (class "Default")
      (node (ref "COM0") (pin "4") (pinfunction "4_4") (pintype "passive+no_connect"))
    )
    (net (code "198") (name "unconnected-(COM0-Pad6)") (class "Default")
      (node (ref "COM0") (pin "6") (pinfunction "6_6") (pintype "passive+no_connect"))
    )
    (net (code "199") (name "unconnected-(COM0-Pad9)") (class "Default")
      (node (ref "COM0") (pin "9") (pinfunction "9_9") (pintype "passive+no_connect"))
    )
    (net (code "200") (name "unconnected-(LAN-PadC)") (class "Default")
      (node (ref "LAN") (pin "C") (pinfunction "C_C") (pintype "passive+no_connect"))
    )
    (net (code "201") (name "unconnected-(LAN-PadD)") (class "Default")
      (node (ref "LAN") (pin "D") (pinfunction "D_D") (pintype "passive+no_connect"))
    )
    (net (code "202") (name "unconnected-(LCD-Pad1)") (class "Default")
      (node (ref "LCD") (pin "1") (pintype "passive+no_connect"))
    )
    (net (code "203") (name "unconnected-(S1-Pad1)") (class "Default")
      (node (ref "S1") (pin "1") (pinfunction "1_1") (pintype "passive+no_connect"))
    )
    (net (code "204") (name "unconnected-(S1-Pad2)") (class "Default")
      (node (ref "S1") (pin "2") (pinfunction "2_2") (pintype "passive+no_connect"))
    )
    (net (code "205") (name "unconnected-(S1-Pad5)") (class "Default")
      (node (ref "S1") (pin "5") (pinfunction "5_5") (pintype "passive+no_connect"))
    )
    (net (code "206") (name "unconnected-(SW-Pad1)") (class "Default")
      (node (ref "SW") (pin "1") (pinfunction "1_1") (pintype "passive+no_connect"))
    )
    (net (code "207") (name "unconnected-(SW-Pad4)") (class "Default")
      (node (ref "SW") (pin "4") (pinfunction "4_4") (pintype "passive+no_connect"))
    )
    (net (code "208") (name "unconnected-(SW-Pad5)") (class "Default")
      (node (ref "SW") (pin "5") (pinfunction "5_5") (pintype "passive+no_connect"))
    )
    (net (code "209") (name "unconnected-(U2-Vout-Pad2)") (class "Default")
      (node (ref "U2") (pin "2") (pinfunction "Vout_2") (pintype "passive"))
    )
    (net (code "210") (name "unconnected-(U3-Vout-Pad2)") (class "Default")
      (node (ref "U3") (pin "2") (pinfunction "Vout_2") (pintype "passive"))
    )
    (net (code "211") (name "unconnected-(U5-CLK20MO-Pad59)") (class "Default")
      (node (ref "U5") (pin "59") (pinfunction "CLK20MO_59") (pintype "passive+no_connect"))
    )
    (net (code "212") (name "unconnected-(U5-COL-Pad44)") (class "Default")
      (node (ref "U5") (pin "44") (pinfunction "COL_44") (pintype "passive+no_connect"))
    )
    (net (code "213") (name "unconnected-(U5-CRS-Pad43)") (class "Default")
      (node (ref "U5") (pin "43") (pinfunction "CRS_43") (pintype "passive+no_connect"))
    )
    (net (code "214") (name "unconnected-(U5-DUP#-Pad61)") (class "Default")
      (node (ref "U5") (pin "61") (pinfunction "DUP#_61") (pintype "passive+no_connect"))
    )
    (net (code "215") (name "unconnected-(U5-EECK-Pad66)") (class "Default")
      (node (ref "U5") (pin "66") (pinfunction "EECK_66") (pintype "passive+no_connect"))
    )
    (net (code "216") (name "unconnected-(U5-EEDI-Pad64)") (class "Default")
      (node (ref "U5") (pin "64") (pinfunction "EEDI_64") (pintype "passive+no_connect"))
    )
    (net (code "217") (name "unconnected-(U5-EEDO-Pad65)") (class "Default")
      (node (ref "U5") (pin "65") (pinfunction "EEDO_65") (pintype "passive+no_connect"))
    )
    (net (code "218") (name "unconnected-(U5-GPIO0-Pad68)") (class "Default")
      (node (ref "U5") (pin "68") (pinfunction "GPIO0_68") (pintype "passive+no_connect"))
    )
    (net (code "219") (name "unconnected-(U5-GPIO1-Pad69)") (class "Default")
      (node (ref "U5") (pin "69") (pinfunction "GPIO1_69") (pintype "passive+no_connect"))
    )
    (net (code "220") (name "unconnected-(U5-GPIO2-Pad70)") (class "Default")
      (node (ref "U5") (pin "70") (pinfunction "GPIO2_70") (pintype "passive+no_connect"))
    )
    (net (code "221") (name "unconnected-(U5-GPIO3-Pad71)") (class "Default")
      (node (ref "U5") (pin "71") (pinfunction "GPIO3_71") (pintype "passive+no_connect"))
    )
    (net (code "222") (name "unconnected-(U5-IO16-Pad91)") (class "Default")
      (node (ref "U5") (pin "91") (pinfunction "IO16_91") (pintype "passive+no_connect"))
    )
    (net (code "223") (name "unconnected-(U5-LINK_I-Pad37)") (class "Default")
      (node (ref "U5") (pin "37") (pinfunction "LINK_I_37") (pintype "passive+no_connect"))
    )
    (net (code "224") (name "unconnected-(U5-LINK_O-Pad78)") (class "Default")
      (node (ref "U5") (pin "78") (pinfunction "LINK_O_78") (pintype "passive"))
    )
    (net (code "225") (name "unconnected-(U5-MDC-Pad57)") (class "Default")
      (node (ref "U5") (pin "57") (pinfunction "MDC_57") (pintype "passive+no_connect"))
    )
    (net (code "226") (name "unconnected-(U5-MDIO-Pad56)") (class "Default")
      (node (ref "U5") (pin "56") (pinfunction "MDIO_56") (pintype "passive+no_connect"))
    )
    (net (code "227") (name "unconnected-(U5-NC-Pad74)") (class "Default")
      (node (ref "U5") (pin "74") (pinfunction "NC_74") (pintype "passive+no_connect"))
    )
    (net (code "228") (name "unconnected-(U5-NC-Pad75)") (class "Default")
      (node (ref "U5") (pin "75") (pinfunction "NC_75") (pintype "passive+no_connect"))
    )
    (net (code "229") (name "unconnected-(U5-NC-Pad77)") (class "Default")
      (node (ref "U5") (pin "77") (pinfunction "NC_77") (pintype "passive+no_connect"))
    )
    (net (code "230") (name "unconnected-(U5-RXD0-Pad38)") (class "Default")
      (node (ref "U5") (pin "38") (pinfunction "RXD0_38") (pintype "passive+no_connect"))
    )
    (net (code "231") (name "unconnected-(U5-RXD1-Pad39)") (class "Default")
      (node (ref "U5") (pin "39") (pinfunction "RXD1_39") (pintype "passive+no_connect"))
    )
    (net (code "232") (name "unconnected-(U5-RXD2-Pad40)") (class "Default")
      (node (ref "U5") (pin "40") (pinfunction "RXD2_40") (pintype "passive+no_connect"))
    )
    (net (code "233") (name "unconnected-(U5-RXD3-Pad41)") (class "Default")
      (node (ref "U5") (pin "41") (pinfunction "RXD3_41") (pintype "passive+no_connect"))
    )
    (net (code "234") (name "unconnected-(U5-RX_CLK-Pad47)") (class "Default")
      (node (ref "U5") (pin "47") (pinfunction "RX_CLK_47") (pintype "passive+no_connect"))
    )
    (net (code "235") (name "unconnected-(U5-RX_DV-Pad45)") (class "Default")
      (node (ref "U5") (pin "45") (pinfunction "RX_DV_45") (pintype "passive+no_connect"))
    )
    (net (code "236") (name "unconnected-(U5-RX_ER-Pad46)") (class "Default")
      (node (ref "U5") (pin "46") (pinfunction "RX_ER_46") (pintype "passive+no_connect"))
    )
    (net (code "237") (name "unconnected-(U5-SD-Pad24)") (class "Default")
      (node (ref "U5") (pin "24") (pinfunction "SD_24") (pintype "passive+no_connect"))
    )
    (net (code "238") (name "unconnected-(U5-TXD0-Pad50)") (class "Default")
      (node (ref "U5") (pin "50") (pinfunction "TXD0_50") (pintype "passive+no_connect"))
    )
    (net (code "239") (name "unconnected-(U5-TXD1-Pad51)") (class "Default")
      (node (ref "U5") (pin "51") (pinfunction "TXD1_51") (pintype "passive+no_connect"))
    )
    (net (code "240") (name "unconnected-(U5-TXD2-Pad52)") (class "Default")
      (node (ref "U5") (pin "52") (pinfunction "TXD2_52") (pintype "passive+no_connect"))
    )
    (net (code "241") (name "unconnected-(U5-TXD3-Pad53)") (class "Default")
      (node (ref "U5") (pin "53") (pinfunction "TXD3_53") (pintype "passive+no_connect"))
    )
    (net (code "242") (name "unconnected-(U5-TX_CLK-Pad49)") (class "Default")
      (node (ref "U5") (pin "49") (pinfunction "TX_CLK_49") (pintype "passive+no_connect"))
    )
    (net (code "243") (name "unconnected-(U5-TX_EN-Pad54)") (class "Default")
      (node (ref "U5") (pin "54") (pinfunction "TX_EN_54") (pintype "passive+no_connect"))
    )
    (net (code "244") (name "unconnected-(U5-WACKUP-Pad79)") (class "Default")
      (node (ref "U5") (pin "79") (pinfunction "WACKUP_79") (pintype "passive"))
    )
  )
)
